# LED_matrix_Keyboard.net
KiCad netlist of a schematic drawn in EAGLE
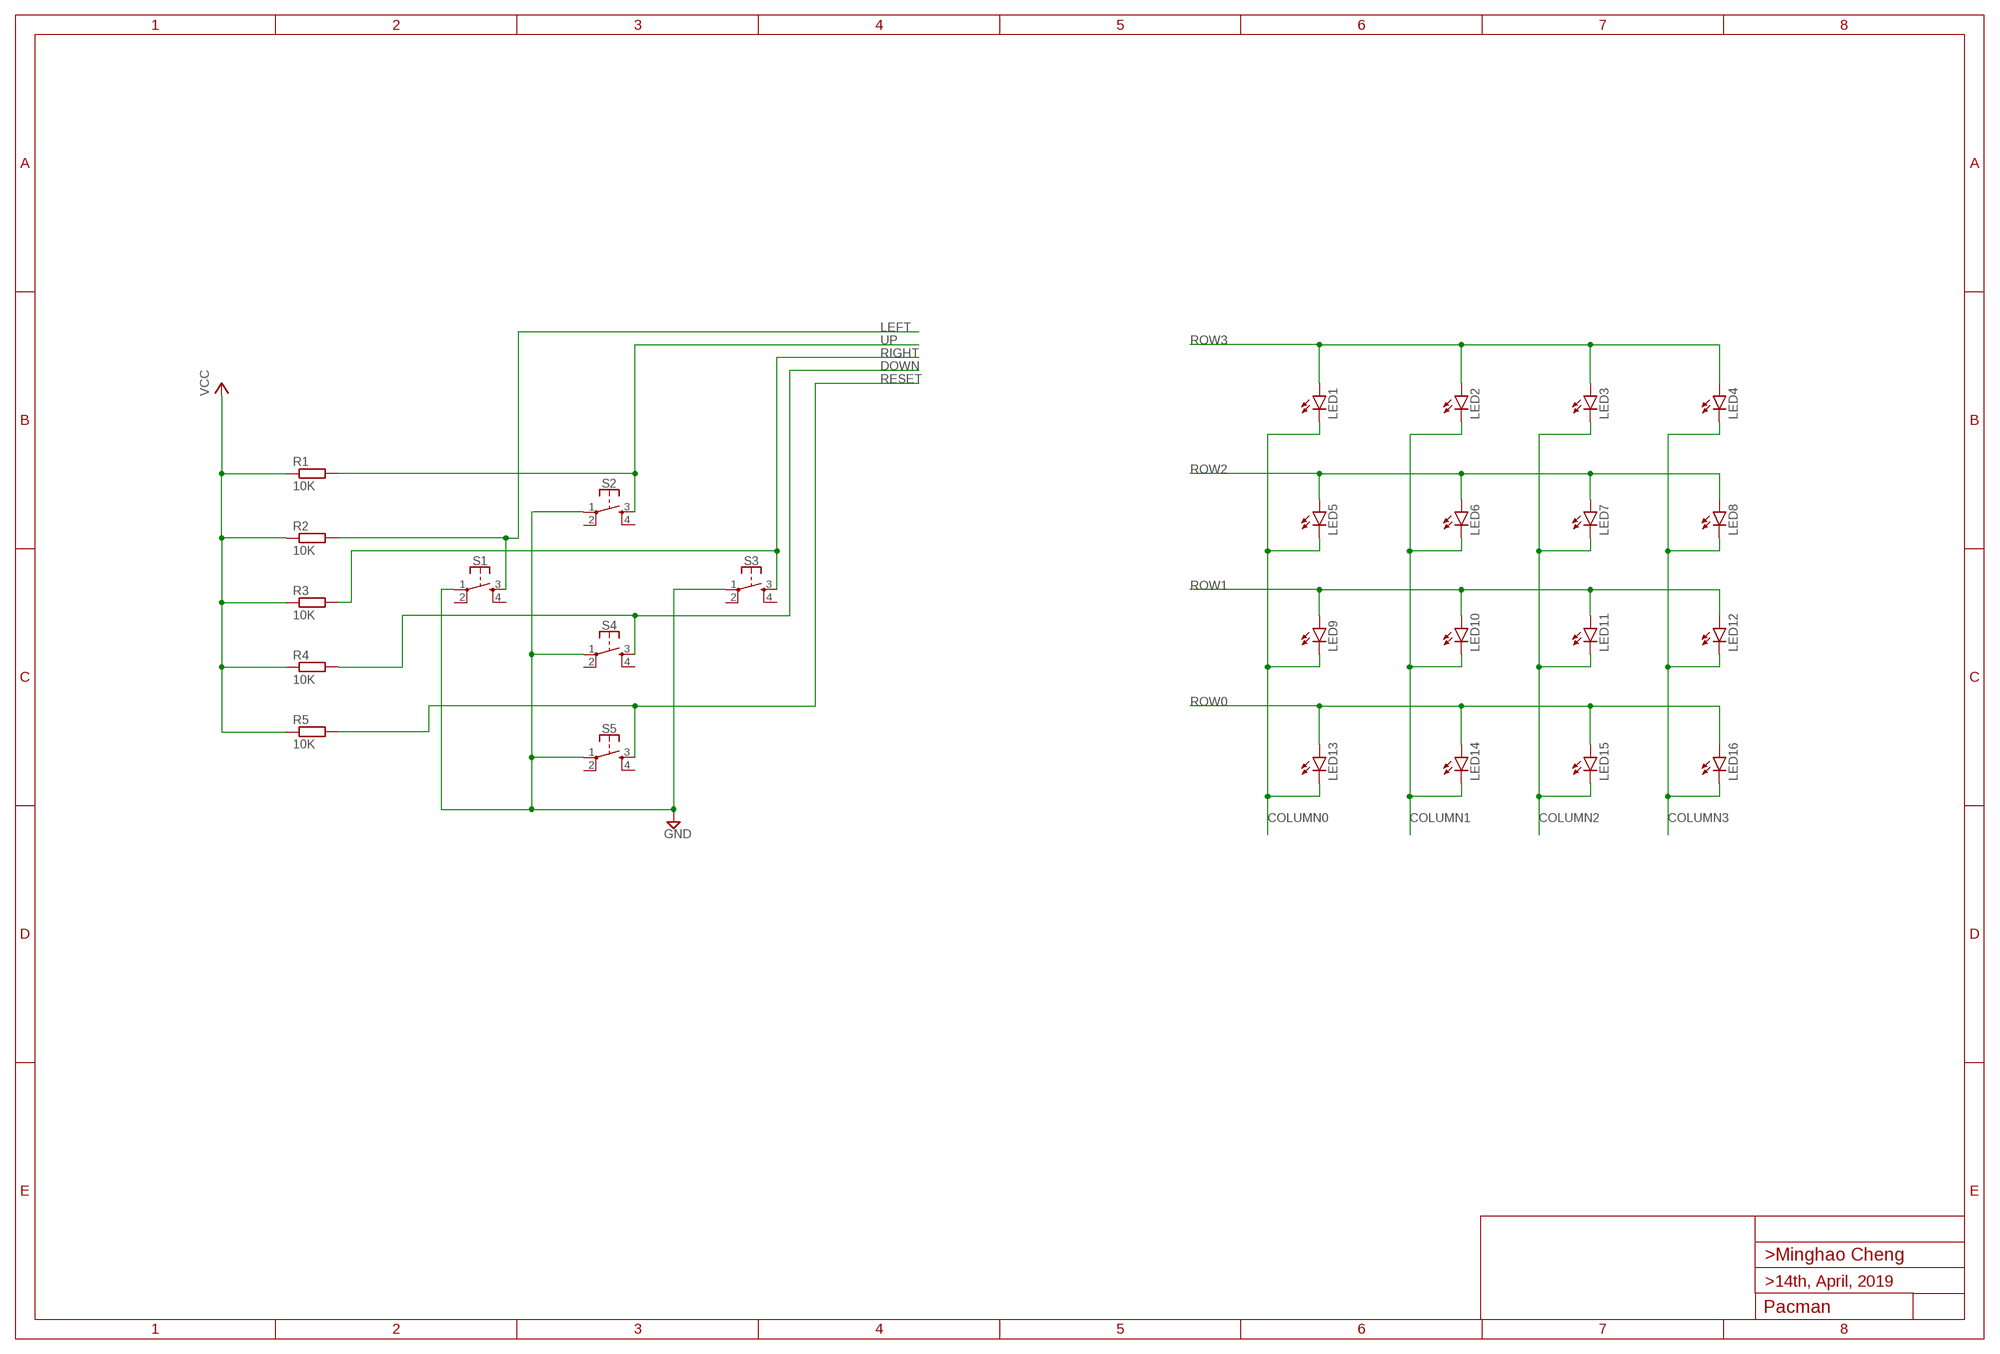
[diagram p0: schematic, sheet 1]

(export (version "E")
  (design (tool "Eeschema 10.0.6"))
  (components
    (comp (ref "LED1")
      (value "LED5MM")
      (footprint "eagle-import:LED5MM")
      (libsource (lib "eagle-import") (part "LED5MM"))
    )
    (comp (ref "LED2")
      (value "LED5MM")
      (footprint "eagle-import:LED5MM")
      (libsource (lib "eagle-import") (part "LED5MM"))
    )
    (comp (ref "LED3")
      (value "LED5MM")
      (footprint "eagle-import:LED5MM")
      (libsource (lib "eagle-import") (part "LED5MM"))
    )
    (comp (ref "LED4")
      (value "LED5MM")
      (footprint "eagle-import:LED5MM")
      (libsource (lib "eagle-import") (part "LED5MM"))
    )
    (comp (ref "LED5")
      (value "LED5MM")
      (footprint "eagle-import:LED5MM")
      (libsource (lib "eagle-import") (part "LED5MM"))
    )
    (comp (ref "LED6")
      (value "LED5MM")
      (footprint "eagle-import:LED5MM")
      (libsource (lib "eagle-import") (part "LED5MM"))
    )
    (comp (ref "LED7")
      (value "LED5MM")
      (footprint "eagle-import:LED5MM")
      (libsource (lib "eagle-import") (part "LED5MM"))
    )
    (comp (ref "LED8")
      (value "LED5MM")
      (footprint "eagle-import:LED5MM")
      (libsource (lib "eagle-import") (part "LED5MM"))
    )
    (comp (ref "LED9")
      (value "LED5MM")
      (footprint "eagle-import:LED5MM")
      (libsource (lib "eagle-import") (part "LED5MM"))
    )
    (comp (ref "LED10")
      (value "LED5MM")
      (footprint "eagle-import:LED5MM")
      (libsource (lib "eagle-import") (part "LED5MM"))
    )
    (comp (ref "LED11")
      (value "LED5MM")
      (footprint "eagle-import:LED5MM")
      (libsource (lib "eagle-import") (part "LED5MM"))
    )
    (comp (ref "LED12")
      (value "LED5MM")
      (footprint "eagle-import:LED5MM")
      (libsource (lib "eagle-import") (part "LED5MM"))
    )
    (comp (ref "LED13")
      (value "LED5MM")
      (footprint "eagle-import:LED5MM")
      (libsource (lib "eagle-import") (part "LED5MM"))
    )
    (comp (ref "LED14")
      (value "LED5MM")
      (footprint "eagle-import:LED5MM")
      (libsource (lib "eagle-import") (part "LED5MM"))
    )
    (comp (ref "LED15")
      (value "LED5MM")
      (footprint "eagle-import:LED5MM")
      (libsource (lib "eagle-import") (part "LED5MM"))
    )
    (comp (ref "LED16")
      (value "LED5MM")
      (footprint "eagle-import:LED5MM")
      (libsource (lib "eagle-import") (part "LED5MM"))
    )
    (comp (ref "R1")
      (value "10K")
      (footprint "eagle-import:R0805")
      (libsource (lib "eagle-import") (part "R-EU_R0805"))
    )
    (comp (ref "R2")
      (value "10K")
      (footprint "eagle-import:R0805")
      (libsource (lib "eagle-import") (part "R-EU_R0805"))
    )
    (comp (ref "R3")
      (value "10K")
      (footprint "eagle-import:R0805")
      (libsource (lib "eagle-import") (part "R-EU_R0805"))
    )
    (comp (ref "R4")
      (value "10K")
      (footprint "eagle-import:R0805")
      (libsource (lib "eagle-import") (part "R-EU_R0805"))
    )
    (comp (ref "R5")
      (value "10K")
      (footprint "eagle-import:R0805")
      (libsource (lib "eagle-import") (part "R-EU_R0805"))
    )
    (comp (ref "S1")
      (value "MOMENTARY-SWITCH-SPST-2-SMD-5.2MM")
      (footprint "eagle-import:TACTILE_SWITCH_SMD_5.2MM")
      (libsource (lib "eagle-import") (part "MOMENTARY-SWITCH-SPST-2-SMD-5.2MM"))
    )
    (comp (ref "S2")
      (value "MOMENTARY-SWITCH-SPST-2-SMD-5.2MM")
      (footprint "eagle-import:TACTILE_SWITCH_SMD_5.2MM")
      (libsource (lib "eagle-import") (part "MOMENTARY-SWITCH-SPST-2-SMD-5.2MM"))
    )
    (comp (ref "S3")
      (value "MOMENTARY-SWITCH-SPST-2-SMD-5.2MM")
      (footprint "eagle-import:TACTILE_SWITCH_SMD_5.2MM")
      (libsource (lib "eagle-import") (part "MOMENTARY-SWITCH-SPST-2-SMD-5.2MM"))
    )
    (comp (ref "S4")
      (value "MOMENTARY-SWITCH-SPST-2-SMD-5.2MM")
      (footprint "eagle-import:TACTILE_SWITCH_SMD_5.2MM")
      (libsource (lib "eagle-import") (part "MOMENTARY-SWITCH-SPST-2-SMD-5.2MM"))
    )
    (comp (ref "S5")
      (value "MOMENTARY-SWITCH-SPST-2-SMD-5.2MM")
      (footprint "eagle-import:TACTILE_SWITCH_SMD_5.2MM")
      (libsource (lib "eagle-import") (part "MOMENTARY-SWITCH-SPST-2-SMD-5.2MM"))
    )
  )
  (nets
    (net (code "1") (name "/COLUMN0") (class "Default")
      (node (ref "LED1") (pin "K") (pinfunction "C_K") (pintype "passive"))
      (node (ref "LED13") (pin "K") (pinfunction "C_K") (pintype "passive"))
      (node (ref "LED5") (pin "K") (pinfunction "C_K") (pintype "passive"))
      (node (ref "LED9") (pin "K") (pinfunction "C_K") (pintype "passive"))
    )
    (net (code "2") (name "/COLUMN1") (class "Default")
      (node (ref "LED10") (pin "K") (pinfunction "C_K") (pintype "passive"))
      (node (ref "LED14") (pin "K") (pinfunction "C_K") (pintype "passive"))
      (node (ref "LED2") (pin "K") (pinfunction "C_K") (pintype "passive"))
      (node (ref "LED6") (pin "K") (pinfunction "C_K") (pintype "passive"))
    )
    (net (code "3") (name "/COLUMN2") (class "Default")
      (node (ref "LED11") (pin "K") (pinfunction "C_K") (pintype "passive"))
      (node (ref "LED15") (pin "K") (pinfunction "C_K") (pintype "passive"))
      (node (ref "LED3") (pin "K") (pinfunction "C_K") (pintype "passive"))
      (node (ref "LED7") (pin "K") (pinfunction "C_K") (pintype "passive"))
    )
    (net (code "4") (name "/COLUMN3") (class "Default")
      (node (ref "LED12") (pin "K") (pinfunction "C_K") (pintype "passive"))
      (node (ref "LED16") (pin "K") (pinfunction "C_K") (pintype "passive"))
      (node (ref "LED4") (pin "K") (pinfunction "C_K") (pintype "passive"))
      (node (ref "LED8") (pin "K") (pinfunction "C_K") (pintype "passive"))
    )
    (net (code "5") (name "/DOWN") (class "Default")
      (node (ref "R4") (pin "2") (pinfunction "2_2") (pintype "passive"))
      (node (ref "S4") (pin "3") (pinfunction "3_3") (pintype "passive"))
    )
    (net (code "6") (name "/LEFT") (class "Default")
      (node (ref "R2") (pin "2") (pinfunction "2_2") (pintype "passive"))
      (node (ref "S1") (pin "3") (pinfunction "3_3") (pintype "passive"))
    )
    (net (code "7") (name "/RESET") (class "Default")
      (node (ref "R5") (pin "2") (pinfunction "2_2") (pintype "passive"))
      (node (ref "S5") (pin "3") (pinfunction "3_3") (pintype "passive"))
    )
    (net (code "8") (name "/RIGHT") (class "Default")
      (node (ref "R3") (pin "2") (pinfunction "2_2") (pintype "passive"))
      (node (ref "S3") (pin "3") (pinfunction "3_3") (pintype "passive"))
    )
    (net (code "9") (name "/ROW0") (class "Default")
      (node (ref "LED13") (pin "A") (pinfunction "A_A") (pintype "passive"))
      (node (ref "LED14") (pin "A") (pinfunction "A_A") (pintype "passive"))
      (node (ref "LED15") (pin "A") (pinfunction "A_A") (pintype "passive"))
      (node (ref "LED16") (pin "A") (pinfunction "A_A") (pintype "passive"))
    )
    (net (code "10") (name "/ROW1") (class "Default")
      (node (ref "LED10") (pin "A") (pinfunction "A_A") (pintype "passive"))
      (node (ref "LED11") (pin "A") (pinfunction "A_A") (pintype "passive"))
      (node (ref "LED12") (pin "A") (pinfunction "A_A") (pintype "passive"))
      (node (ref "LED9") (pin "A") (pinfunction "A_A") (pintype "passive"))
    )
    (net (code "11") (name "/ROW2") (class "Default")
      (node (ref "LED5") (pin "A") (pinfunction "A_A") (pintype "passive"))
      (node (ref "LED6") (pin "A") (pinfunction "A_A") (pintype "passive"))
      (node (ref "LED7") (pin "A") (pinfunction "A_A") (pintype "passive"))
      (node (ref "LED8") (pin "A") (pinfunction "A_A") (pintype "passive"))
    )
    (net (code "12") (name "/ROW3") (class "Default")
      (node (ref "LED1") (pin "A") (pinfunction "A_A") (pintype "passive"))
      (node (ref "LED2") (pin "A") (pinfunction "A_A") (pintype "passive"))
      (node (ref "LED3") (pin "A") (pinfunction "A_A") (pintype "passive"))
      (node (ref "LED4") (pin "A") (pinfunction "A_A") (pintype "passive"))
    )
    (net (code "13") (name "/UP") (class "Default")
      (node (ref "R1") (pin "2") (pinfunction "2_2") (pintype "passive"))
      (node (ref "S2") (pin "3") (pinfunction "3_3") (pintype "passive"))
    )
    (net (code "14") (name "GND") (class "Default")
      (node (ref "S1") (pin "1") (pinfunction "1_1") (pintype "passive"))
      (node (ref "S2") (pin "1") (pinfunction "1_1") (pintype "passive"))
      (node (ref "S3") (pin "1") (pinfunction "1_1") (pintype "passive"))
      (node (ref "S4") (pin "1") (pinfunction "1_1") (pintype "passive"))
      (node (ref "S5") (pin "1") (pinfunction "1_1") (pintype "passive"))
    )
    (net (code "15") (name "VCC") (class "Default")
      (node (ref "R1") (pin "1") (pinfunction "1_1") (pintype "passive"))
      (node (ref "R2") (pin "1") (pinfunction "1_1") (pintype "passive"))
      (node (ref "R3") (pin "1") (pinfunction "1_1") (pintype "passive"))
      (node (ref "R4") (pin "1") (pinfunction "1_1") (pintype "passive"))
      (node (ref "R5") (pin "1") (pinfunction "1_1") (pintype "passive"))
    )
    (net (code "16") (name "unconnected-(S1-Pad2)") (class "Default")
      (node (ref "S1") (pin "2") (pinfunction "2_2") (pintype "passive"))
    )
    (net (code "17") (name "unconnected-(S1-Pad4)") (class "Default")
      (node (ref "S1") (pin "4") (pinfunction "4_4") (pintype "passive"))
    )
    (net (code "18") (name "unconnected-(S2-Pad2)") (class "Default")
      (node (ref "S2") (pin "2") (pinfunction "2_2") (pintype "passive"))
    )
    (net (code "19") (name "unconnected-(S2-Pad4)") (class "Default")
      (node (ref "S2") (pin "4") (pinfunction "4_4") (pintype "passive"))
    )
    (net (code "20") (name "unconnected-(S3-Pad2)") (class "Default")
      (node (ref "S3") (pin "2") (pinfunction "2_2") (pintype "passive"))
    )
    (net (code "21") (name "unconnected-(S3-Pad4)") (class "Default")
      (node (ref "S3") (pin "4") (pinfunction "4_4") (pintype "passive"))
    )
    (net (code "22") (name "unconnected-(S4-Pad2)") (class "Default")
      (node (ref "S4") (pin "2") (pinfunction "2_2") (pintype "passive"))
    )
    (net (code "23") (name "unconnected-(S4-Pad4)") (class "Default")
      (node (ref "S4") (pin "4") (pinfunction "4_4") (pintype "passive"))
    )
    (net (code "24") (name "unconnected-(S5-Pad2)") (class "Default")
      (node (ref "S5") (pin "2") (pinfunction "2_2") (pintype "passive"))
    )
    (net (code "25") (name "unconnected-(S5-Pad4)") (class "Default")
      (node (ref "S5") (pin "4") (pinfunction "4_4") (pintype "passive"))
    )
  )
)
